# ESP32_S3-Mini-1.net
KiCad netlist of a schematic drawn in Altium Designer
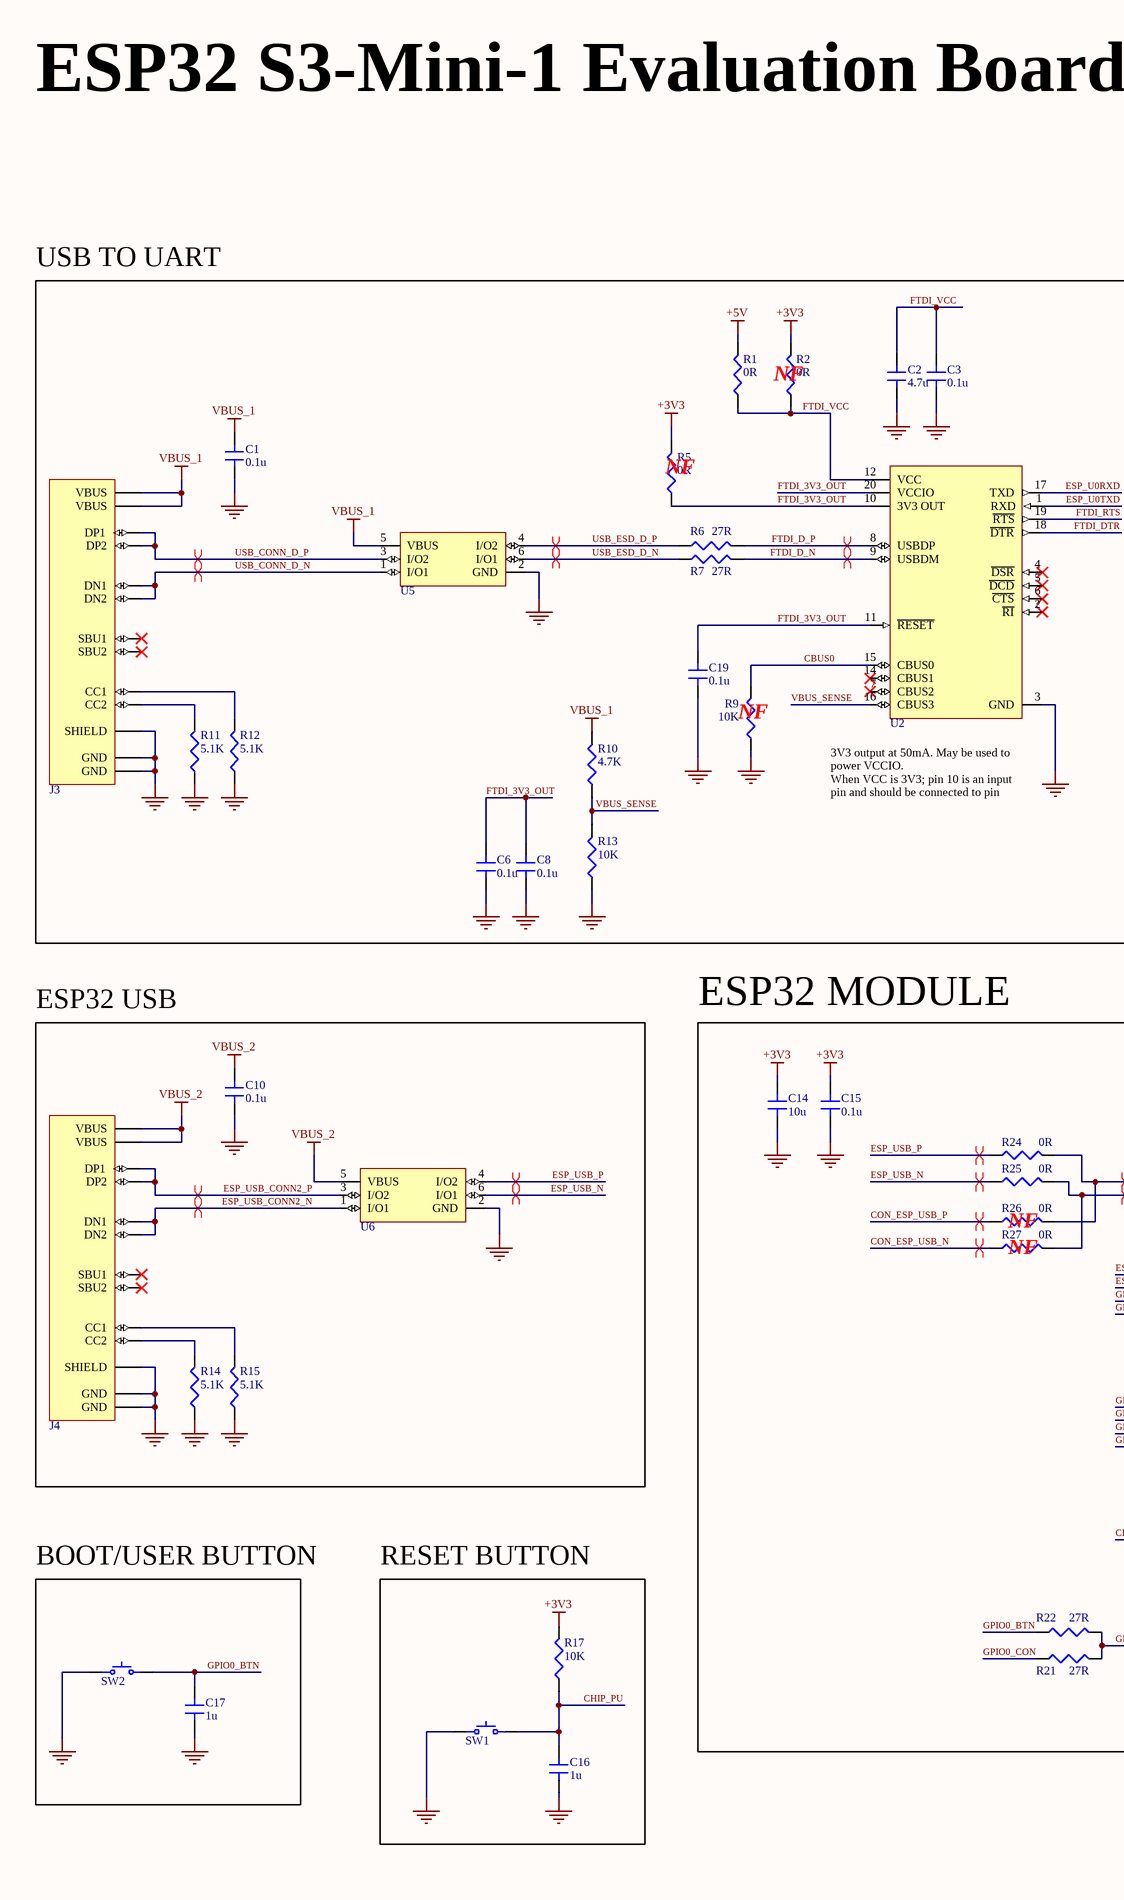
[diagram p0: ESP32 S3-Mini-1.SchDoc, left]
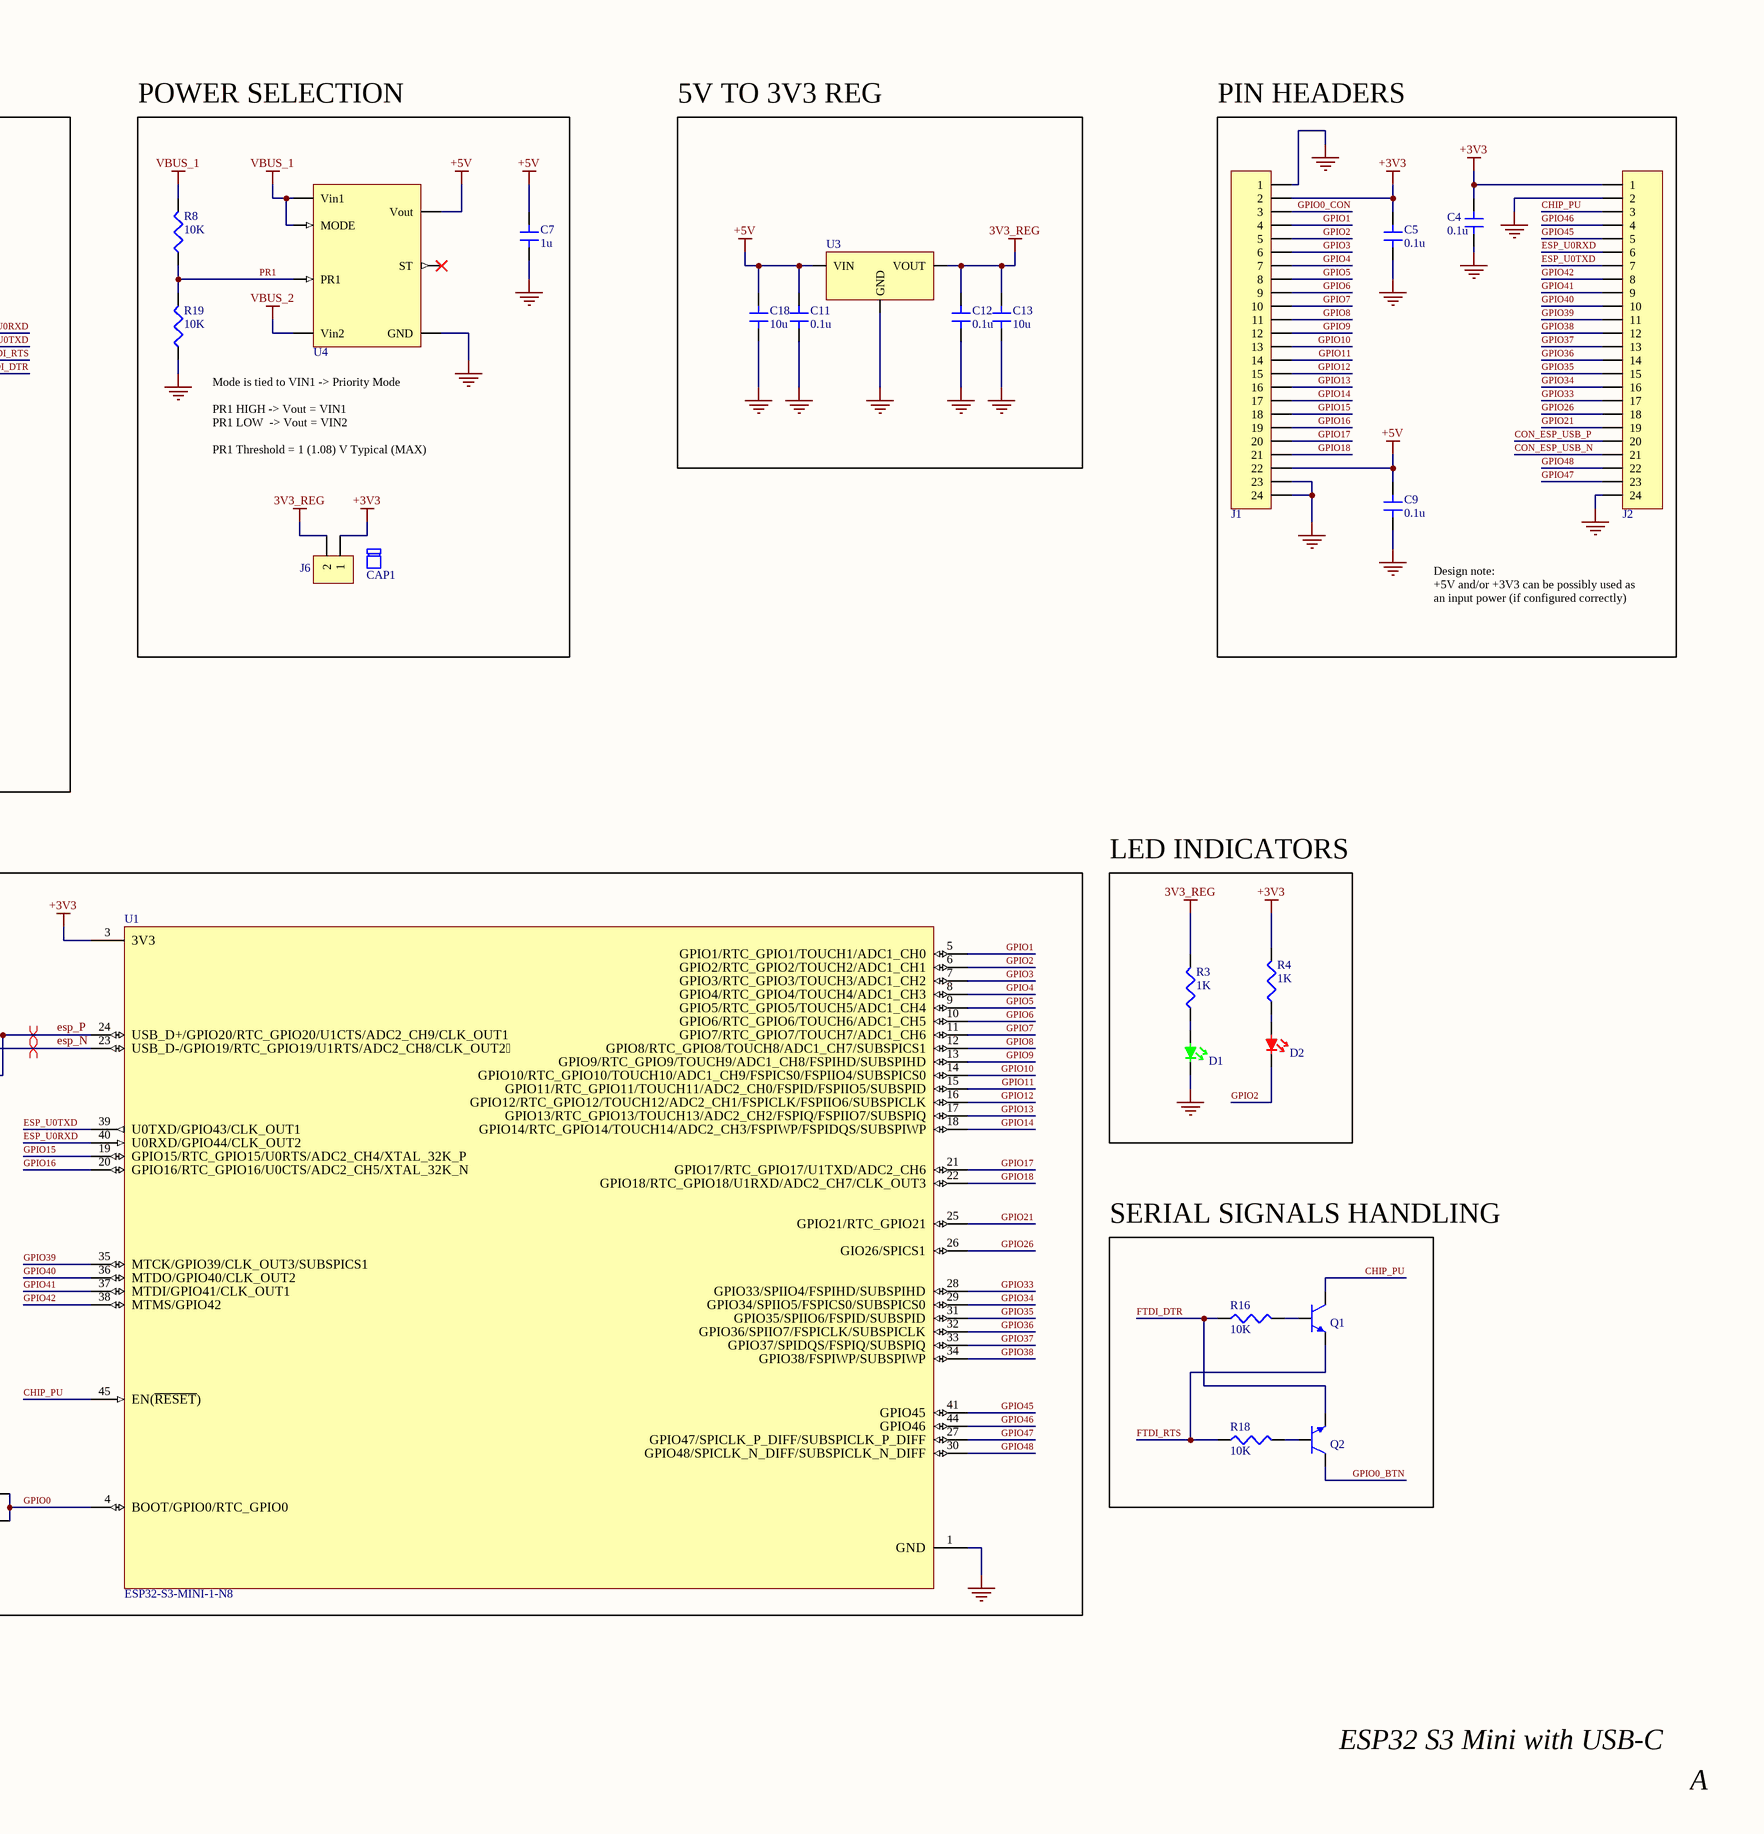
[diagram p1: ESP32 S3-Mini-1.SchDoc, right]

(export (version "E")
  (design (tool "Eeschema 10.0.6"))
  (components
    (comp (ref "C1")
      (value "0.1u")
      (footprint "0603-CAP")
      (description "50V 100nF X7R ±5% 0603 Multilayer Ceramic Capacitors MLCC - SMD/SMT ROHS")
      (fields (field (name "MANUFACTURER") "YAGEO") (field (name "MFR. PART #") "CC0603JRX7R9BB104"))
      (libsource (lib "Symbols") (part "CAP 0.1uF"))
    )
    (comp (ref "C2")
      (value "4.7u")
      (footprint "0603-CAP")
      (description "16V 4.7uF X5R ±10% 0603 Multilayer Ceramic Capacitors MLCC - SMD/SMT ROHS")
      (fields
        (field (name "MANUFACTURER") "Samsung Electro-Mechanics")
        (field (name "MFR. PART #") "CL10A475KO8NNNC")
      )
      (libsource (lib "Symbols") (part "CAP 4.7uF"))
    )
    (comp (ref "C3")
      (value "0.1u")
      (footprint "0603-CAP")
      (description "50V 100nF X7R ±5% 0603 Multilayer Ceramic Capacitors MLCC - SMD/SMT ROHS")
      (fields (field (name "MANUFACTURER") "YAGEO") (field (name "MFR. PART #") "CC0603JRX7R9BB104"))
      (libsource (lib "Symbols") (part "CAP 0.1uF"))
    )
    (comp (ref "C4")
      (value "0.1u")
      (footprint "0603-CAP")
      (description "50V 100nF X7R ±5% 0603 Multilayer Ceramic Capacitors MLCC - SMD/SMT ROHS")
      (fields (field (name "MANUFACTURER") "YAGEO") (field (name "MFR. PART #") "CC0603JRX7R9BB104"))
      (libsource (lib "Symbols") (part "CAP 0.1uF"))
    )
    (comp (ref "C5")
      (value "0.1u")
      (footprint "0603-CAP")
      (description "50V 100nF X7R ±5% 0603 Multilayer Ceramic Capacitors MLCC - SMD/SMT ROHS")
      (fields (field (name "MANUFACTURER") "YAGEO") (field (name "MFR. PART #") "CC0603JRX7R9BB104"))
      (libsource (lib "Symbols") (part "CAP 0.1uF"))
    )
    (comp (ref "C6")
      (value "0.1u")
      (footprint "0603-CAP")
      (description "50V 100nF X7R ±5% 0603 Multilayer Ceramic Capacitors MLCC - SMD/SMT ROHS")
      (fields (field (name "MANUFACTURER") "YAGEO") (field (name "MFR. PART #") "CC0603JRX7R9BB104"))
      (libsource (lib "Symbols") (part "CAP 0.1uF"))
    )
    (comp (ref "C7")
      (value "1u")
      (footprint "0603-CAP")
      (description "16V 1uF X7R ±5% 0603 Multilayer Ceramic Capacitors MLCC - SMD/SMT ROHS")
      (fields (field (name "MANUFACTURER") "YAGEO") (field (name "MFR. PART #") "CC0603JRX7R7BB105"))
      (libsource (lib "Symbols") (part "CAP 1uF"))
    )
    (comp (ref "C8")
      (value "0.1u")
      (footprint "0603-CAP")
      (description "50V 100nF X7R ±5% 0603 Multilayer Ceramic Capacitors MLCC - SMD/SMT ROHS")
      (fields (field (name "MANUFACTURER") "YAGEO") (field (name "MFR. PART #") "CC0603JRX7R9BB104"))
      (libsource (lib "Symbols") (part "CAP 0.1uF"))
    )
    (comp (ref "C9")
      (value "0.1u")
      (footprint "0603-CAP")
      (description "50V 100nF X7R ±5% 0603 Multilayer Ceramic Capacitors MLCC - SMD/SMT ROHS")
      (fields (field (name "MANUFACTURER") "YAGEO") (field (name "MFR. PART #") "CC0603JRX7R9BB104"))
      (libsource (lib "Symbols") (part "CAP 0.1uF"))
    )
    (comp (ref "C10")
      (value "0.1u")
      (footprint "0603-CAP")
      (description "50V 100nF X7R ±5% 0603 Multilayer Ceramic Capacitors MLCC - SMD/SMT ROHS")
      (fields (field (name "MANUFACTURER") "YAGEO") (field (name "MFR. PART #") "CC0603JRX7R9BB104"))
      (libsource (lib "Symbols") (part "CAP 0.1uF"))
    )
    (comp (ref "C11")
      (value "0.1u")
      (footprint "0603-CAP")
      (description "50V 100nF X7R ±5% 0603 Multilayer Ceramic Capacitors MLCC - SMD/SMT ROHS")
      (fields (field (name "MANUFACTURER") "YAGEO") (field (name "MFR. PART #") "CC0603JRX7R9BB104"))
      (libsource (lib "Symbols") (part "CAP 0.1uF"))
    )
    (comp (ref "C12")
      (value "0.1u")
      (footprint "0603-CAP")
      (description "50V 100nF X7R ±5% 0603 Multilayer Ceramic Capacitors MLCC - SMD/SMT ROHS")
      (fields (field (name "MANUFACTURER") "YAGEO") (field (name "MFR. PART #") "CC0603JRX7R9BB104"))
      (libsource (lib "Symbols") (part "CAP 0.1uF"))
    )
    (comp (ref "C13")
      (value "10u")
      (footprint "0603-CAP")
      (description "16V 10uF X5R ±10% 0603 Multilayer Ceramic Capacitors MLCC - SMD/SMT ROHS")
      (fields
        (field (name "MANUFACTURER") "Samsung Electro-Mechanics")
        (field (name "MFR. PART #") "CL10A106KO8NQNC")
      )
      (libsource (lib "Symbols") (part "CAP 10uF"))
    )
    (comp (ref "C14")
      (value "10u")
      (footprint "0603-CAP")
      (description "16V 10uF X5R ±10% 0603 Multilayer Ceramic Capacitors MLCC - SMD/SMT ROHS")
      (fields
        (field (name "MANUFACTURER") "Samsung Electro-Mechanics")
        (field (name "MFR. PART #") "CL10A106KO8NQNC")
      )
      (libsource (lib "Symbols") (part "CAP 10uF"))
    )
    (comp (ref "C15")
      (value "0.1u")
      (footprint "0603-CAP")
      (description "50V 100nF X7R ±5% 0603 Multilayer Ceramic Capacitors MLCC - SMD/SMT ROHS")
      (fields (field (name "MANUFACTURER") "YAGEO") (field (name "MFR. PART #") "CC0603JRX7R9BB104"))
      (libsource (lib "Symbols") (part "CAP 0.1uF"))
    )
    (comp (ref "C16")
      (value "1u")
      (footprint "0603-CAP")
      (description "16V 1uF X7R ±5% 0603 Multilayer Ceramic Capacitors MLCC - SMD/SMT ROHS")
      (fields (field (name "MANUFACTURER") "YAGEO") (field (name "MFR. PART #") "CC0603JRX7R7BB105"))
      (libsource (lib "Symbols") (part "CAP 1uF"))
    )
    (comp (ref "C17")
      (value "1u")
      (footprint "0603-CAP")
      (description "16V 1uF X7R ±5% 0603 Multilayer Ceramic Capacitors MLCC - SMD/SMT ROHS")
      (fields (field (name "MANUFACTURER") "YAGEO") (field (name "MFR. PART #") "CC0603JRX7R7BB105"))
      (libsource (lib "Symbols") (part "CAP 1uF"))
    )
    (comp (ref "C18")
      (value "10u")
      (footprint "0603-CAP")
      (description "16V 10uF X5R ±10% 0603 Multilayer Ceramic Capacitors MLCC - SMD/SMT ROHS")
      (fields
        (field (name "MANUFACTURER") "Samsung Electro-Mechanics")
        (field (name "MFR. PART #") "CL10A106KO8NQNC")
      )
      (libsource (lib "Symbols") (part "CAP 10uF"))
    )
    (comp (ref "C19")
      (value "0.1u")
      (footprint "0603-CAP")
      (description "50V 100nF X7R ±5% 0603 Multilayer Ceramic Capacitors MLCC - SMD/SMT ROHS")
      (fields (field (name "MANUFACTURER") "YAGEO") (field (name "MFR. PART #") "CC0603JRX7R9BB104"))
      (libsource (lib "Symbols") (part "CAP 0.1uF"))
    )
    (comp (ref "CAP1")
      (value "Cap Jumper")
      (description "Open top 3A 2.54mm P=2.54mm Shunts, Jumpers ROHS")
      (fields
        (field (name "MANUFACTURER") "BOOMELE(Boom Precision Elec)")
        (field (name "MFR. PART #") "2.54")
      )
      (libsource (lib "Symbols") (part "Cap Jumper"))
    )
    (comp (ref "D1")
      (value "GREEN")
      (footprint "1206-LED green")
      (fields (field (name "MANUFACTURER") "XINGLIGHT") (field (name "MFR. PART #") "XL-3216UGC"))
      (libsource (lib "Symbols") (part "LED GREEN"))
    )
    (comp (ref "D2")
      (value "RED")
      (footprint "1206-LED red")
      (fields (field (name "MANUFACTURER") "XINGLIGHT") (field (name "MFR. PART #") "XL-3216SURC"))
      (libsource (lib "Symbols") (part "LED RED"))
    )
    (comp (ref "J1")
      (value "1x24P male Pinheaders")
      (footprint "1x24P male pinheader")
      (fields
        (field (name "MANUFACTURER") "XKB Connection")
        (field (name "MFR. PART #") "X6511WV-24H-C60D30")
      )
      (libsource (lib "") (part "1x24P male Pinheaders_1"))
    )
    (comp (ref "J2")
      (value "1x24P male Pinheaders")
      (footprint "1x24P male pinheader")
      (fields
        (field (name "MANUFACTURER") "XKB Connection")
        (field (name "MFR. PART #") "X6511WV-24H-C60D30")
      )
      (libsource (lib "Symbols") (part "1x24P male Pinheaders"))
    )
    (comp (ref "J3")
      (value "USB Type C connector")
      (footprint "USB-C")
      (description "5A 1 16P Female Type-C SMD USB Connectors ROHS")
      (fields
        (field (name "MANUFACTURER") "Korean Hroparts Elec")
        (field (name "MFR. PART #") "TYPE-C-31-M-12")
      )
      (libsource (lib "Symbols") (part "USB Type C connector"))
    )
    (comp (ref "J4")
      (value "USB Type C connector")
      (footprint "USB-C")
      (description "5A 1 16P Female Type-C SMD USB Connectors ROHS")
      (fields
        (field (name "MANUFACTURER") "Korean Hroparts Elec")
        (field (name "MFR. PART #") "TYPE-C-31-M-12")
      )
      (libsource (lib "Symbols") (part "USB Type C connector"))
    )
    (comp (ref "J6")
      (value "1x2P male Pinheaders")
      (footprint "1x2P male pinheader")
      (description "3A Direct Insert Policy 2.54mm 2P 6mm 3mm 2.54mm Single Row 1x2P Plugin,P=2.54mm Pin Headers ROHS")
      (fields (field (name "MANUFACTURER") "DEALON") (field (name "MFR. PART #") "DZ254R-11-02-63"))
      (libsource (lib "Symbols") (part "1x2P male Pinheaders"))
    )
    (comp (ref "Q1")
      (value "BJT Transistor")
      (footprint "SOT-23")
      (description "25V 300mW 120@100mA,1V 1.5A NPN SOT-23 Bipolar (BJT) ROHS")
      (fields
        (field (name "MANUFACTURER") "Jiangsu Changjing Electronics Technology Co., Ltd.")
        (field (name "MFR. PART #") "SS8050-G(RANGE:120-200)")
      )
      (libsource (lib "Symbols") (part "BJT Transistor"))
    )
    (comp (ref "Q2")
      (value "BJT Transistor")
      (footprint "SOT-23")
      (description "25V 300mW 120@100mA,1V 1.5A NPN SOT-23 Bipolar (BJT) ROHS")
      (fields
        (field (name "MANUFACTURER") "Jiangsu Changjing Electronics Technology Co., Ltd.")
        (field (name "MFR. PART #") "SS8050-G(RANGE:120-200)")
      )
      (libsource (lib "Symbols") (part "BJT Transistor"))
    )
    (comp (ref "R1")
      (value "0R")
      (footprint "0402-RES")
      (description "62.5mW Thick Film Resistors 50V ±800ppm/℃ ±1% 0Ω 0402 Chip Resistor - Surface Mount ROHS")
      (fields
        (field (name "MANUFACTURER") "UNI-ROYAL(Uniroyal Elec)")
        (field (name "MFR. PART #") "0402WGF0000TCE")
      )
      (libsource (lib "Symbols") (part "Resistor 0R"))
    )
    (comp (ref "R2")
      (value "0R")
      (footprint "0402-RES")
      (description "62.5mW Thick Film Resistors 50V ±800ppm/℃ ±1% 0Ω 0402 Chip Resistor - Surface Mount ROHS")
      (fields
        (field (name "MANUFACTURER") "UNI-ROYAL(Uniroyal Elec)")
        (field (name "MFR. PART #") "0402WGF0000TCE")
      )
      (libsource (lib "Symbols") (part "Resistor 0R"))
    )
    (comp (ref "R3")
      (value "1K")
      (footprint "0603-RES")
      (description "100mW Thick Film Resistors 75V ±100ppm/℃ ±1% 1kΩ 0603 Chip Resistor - Surface Mount ROHS")
      (fields
        (field (name "MANUFACTURER") "UNI-ROYAL(Uniroyal Elec)")
        (field (name "MFR. PART #") "0603WAF1001T5E")
      )
      (libsource (lib "Symbols") (part "Resistor 1K"))
    )
    (comp (ref "R4")
      (value "1K")
      (footprint "0603-RES")
      (description "100mW Thick Film Resistors 75V ±100ppm/℃ ±1% 1kΩ 0603 Chip Resistor - Surface Mount ROHS")
      (fields
        (field (name "MANUFACTURER") "UNI-ROYAL(Uniroyal Elec)")
        (field (name "MFR. PART #") "0603WAF1001T5E")
      )
      (libsource (lib "Symbols") (part "Resistor 1K"))
    )
    (comp (ref "R5")
      (value "0R")
      (footprint "0402-RES")
      (description "62.5mW Thick Film Resistors 50V ±800ppm/℃ ±1% 0Ω 0402 Chip Resistor - Surface Mount ROHS")
      (fields
        (field (name "MANUFACTURER") "UNI-ROYAL(Uniroyal Elec)")
        (field (name "MFR. PART #") "0402WGF0000TCE")
      )
      (libsource (lib "Symbols") (part "Resistor 0R"))
    )
    (comp (ref "R6")
      (value "27R")
      (footprint "0603-RES")
      (description "100mW Thick Film Resistors 75V ±1% ±200ppm/℃ 27Ω 0603 Chip Resistor - Surface Mount ROHS")
      (fields
        (field (name "MANUFACTURER") "UNI-ROYAL(Uniroyal Elec)")
        (field (name "MFR. PART #") "0603WAF270JT5E")
      )
      (libsource (lib "Symbols") (part "Resistor 27R"))
    )
    (comp (ref "R7")
      (value "27R")
      (footprint "0603-RES")
      (description "100mW Thick Film Resistors 75V ±1% ±200ppm/℃ 27Ω 0603 Chip Resistor - Surface Mount ROHS")
      (fields
        (field (name "MANUFACTURER") "UNI-ROYAL(Uniroyal Elec)")
        (field (name "MFR. PART #") "0603WAF270JT5E")
      )
      (libsource (lib "Symbols") (part "Resistor 27R"))
    )
    (comp (ref "R8")
      (value "10K")
      (footprint "0603-RES")
      (description "100mW Thick Film Resistors 75V ±100ppm/℃ ±1% 10kΩ 0603 Chip Resistor - Surface Mount ROHS")
      (fields
        (field (name "MANUFACTURER") "UNI-ROYAL(Uniroyal Elec)")
        (field (name "MFR. PART #") "0603WAF1002T5E")
      )
      (libsource (lib "Symbols") (part "Resistor 10K"))
    )
    (comp (ref "R9")
      (value "10K")
      (footprint "0603-RES")
      (description "100mW Thick Film Resistors 75V ±100ppm/℃ ±1% 10kΩ 0603 Chip Resistor - Surface Mount ROHS")
      (fields
        (field (name "MANUFACTURER") "UNI-ROYAL(Uniroyal Elec)")
        (field (name "MFR. PART #") "0603WAF1002T5E")
      )
      (libsource (lib "Symbols") (part "Resistor 10K"))
    )
    (comp (ref "R10")
      (value "4.7K")
      (footprint "0603-RES")
      (description "100mW Thick Film Resistors 75V ±100ppm/℃ ±1% 4.7kΩ 0603 Chip Resistor - Surface Mount ROHS")
      (fields
        (field (name "MANUFACTURER") "UNI-ROYAL(Uniroyal Elec)")
        (field (name "MFR. PART #") "0603WAF4701T5E")
      )
      (libsource (lib "Symbols") (part "Resistor 4.7K"))
    )
    (comp (ref "R11")
      (value "5.1K")
      (footprint "0603-RES")
      (description "100mW Thick Film Resistors 75V ±100ppm/℃ ±5% 5.1kΩ 0603 Chip Resistor - Surface Mount ROHS")
      (fields
        (field (name "MANUFACTURER") "UNI-ROYAL(Uniroyal Elec)")
        (field (name "MFR. PART #") "0603WAJ0512T5E")
      )
      (libsource (lib "Symbols") (part "Resistor 5.1K"))
    )
    (comp (ref "R12")
      (value "5.1K")
      (footprint "0603-RES")
      (description "100mW Thick Film Resistors 75V ±100ppm/℃ ±5% 5.1kΩ 0603 Chip Resistor - Surface Mount ROHS")
      (fields
        (field (name "MANUFACTURER") "UNI-ROYAL(Uniroyal Elec)")
        (field (name "MFR. PART #") "0603WAJ0512T5E")
      )
      (libsource (lib "Symbols") (part "Resistor 5.1K"))
    )
    (comp (ref "R13")
      (value "10K")
      (footprint "0603-RES")
      (description "100mW Thick Film Resistors 75V ±100ppm/℃ ±1% 10kΩ 0603 Chip Resistor - Surface Mount ROHS")
      (fields
        (field (name "MANUFACTURER") "UNI-ROYAL(Uniroyal Elec)")
        (field (name "MFR. PART #") "0603WAF1002T5E")
      )
      (libsource (lib "Symbols") (part "Resistor 10K"))
    )
    (comp (ref "R14")
      (value "5.1K")
      (footprint "0603-RES")
      (description "100mW Thick Film Resistors 75V ±100ppm/℃ ±5% 5.1kΩ 0603 Chip Resistor - Surface Mount ROHS")
      (fields
        (field (name "MANUFACTURER") "UNI-ROYAL(Uniroyal Elec)")
        (field (name "MFR. PART #") "0603WAJ0512T5E")
      )
      (libsource (lib "Symbols") (part "Resistor 5.1K"))
    )
    (comp (ref "R15")
      (value "5.1K")
      (footprint "0603-RES")
      (description "100mW Thick Film Resistors 75V ±100ppm/℃ ±5% 5.1kΩ 0603 Chip Resistor - Surface Mount ROHS")
      (fields
        (field (name "MANUFACTURER") "UNI-ROYAL(Uniroyal Elec)")
        (field (name "MFR. PART #") "0603WAJ0512T5E")
      )
      (libsource (lib "Symbols") (part "Resistor 5.1K"))
    )
    (comp (ref "R16")
      (value "10K")
      (footprint "0603-RES")
      (description "100mW Thick Film Resistors 75V ±100ppm/℃ ±1% 10kΩ 0603 Chip Resistor - Surface Mount ROHS")
      (fields
        (field (name "MANUFACTURER") "UNI-ROYAL(Uniroyal Elec)")
        (field (name "MFR. PART #") "0603WAF1002T5E")
      )
      (libsource (lib "Symbols") (part "Resistor 10K"))
    )
    (comp (ref "R17")
      (value "10K")
      (footprint "0603-RES")
      (description "100mW Thick Film Resistors 75V ±100ppm/℃ ±1% 10kΩ 0603 Chip Resistor - Surface Mount ROHS")
      (fields
        (field (name "MANUFACTURER") "UNI-ROYAL(Uniroyal Elec)")
        (field (name "MFR. PART #") "0603WAF1002T5E")
      )
      (libsource (lib "Symbols") (part "Resistor 10K"))
    )
    (comp (ref "R18")
      (value "10K")
      (footprint "0603-RES")
      (description "100mW Thick Film Resistors 75V ±100ppm/℃ ±1% 10kΩ 0603 Chip Resistor - Surface Mount ROHS")
      (fields
        (field (name "MANUFACTURER") "UNI-ROYAL(Uniroyal Elec)")
        (field (name "MFR. PART #") "0603WAF1002T5E")
      )
      (libsource (lib "Symbols") (part "Resistor 10K"))
    )
    (comp (ref "R19")
      (value "10K")
      (footprint "0603-RES")
      (description "100mW Thick Film Resistors 75V ±100ppm/℃ ±1% 10kΩ 0603 Chip Resistor - Surface Mount ROHS")
      (fields
        (field (name "MANUFACTURER") "UNI-ROYAL(Uniroyal Elec)")
        (field (name "MFR. PART #") "0603WAF1002T5E")
      )
      (libsource (lib "Symbols") (part "Resistor 10K"))
    )
    (comp (ref "R21")
      (value "27R")
      (footprint "0603-RES")
      (description "100mW Thick Film Resistors 75V ±1% ±200ppm/℃ 27Ω 0603 Chip Resistor - Surface Mount ROHS")
      (fields
        (field (name "MANUFACTURER") "UNI-ROYAL(Uniroyal Elec)")
        (field (name "MFR. PART #") "0603WAF270JT5E")
      )
      (libsource (lib "Symbols") (part "Resistor 27R"))
    )
    (comp (ref "R22")
      (value "27R")
      (footprint "0603-RES")
      (description "100mW Thick Film Resistors 75V ±1% ±200ppm/℃ 27Ω 0603 Chip Resistor - Surface Mount ROHS")
      (fields
        (field (name "MANUFACTURER") "UNI-ROYAL(Uniroyal Elec)")
        (field (name "MFR. PART #") "0603WAF270JT5E")
      )
      (libsource (lib "Symbols") (part "Resistor 27R"))
    )
    (comp (ref "R24")
      (value "0R")
      (footprint "0402-RES")
      (description "62.5mW Thick Film Resistors 50V ±800ppm/℃ ±1% 0Ω 0402 Chip Resistor - Surface Mount ROHS")
      (fields
        (field (name "MANUFACTURER") "UNI-ROYAL(Uniroyal Elec)")
        (field (name "MFR. PART #") "0402WGF0000TCE")
      )
      (libsource (lib "Symbols") (part "Resistor 0R"))
    )
    (comp (ref "R25")
      (value "0R")
      (footprint "0402-RES")
      (description "62.5mW Thick Film Resistors 50V ±800ppm/℃ ±1% 0Ω 0402 Chip Resistor - Surface Mount ROHS")
      (fields
        (field (name "MANUFACTURER") "UNI-ROYAL(Uniroyal Elec)")
        (field (name "MFR. PART #") "0402WGF0000TCE")
      )
      (libsource (lib "Symbols") (part "Resistor 0R"))
    )
    (comp (ref "R26")
      (value "0R")
      (footprint "0402-RES")
      (description "62.5mW Thick Film Resistors 50V ±800ppm/℃ ±1% 0Ω 0402 Chip Resistor - Surface Mount ROHS")
      (fields
        (field (name "MANUFACTURER") "UNI-ROYAL(Uniroyal Elec)")
        (field (name "MFR. PART #") "0402WGF0000TCE")
      )
      (libsource (lib "Symbols") (part "Resistor 0R"))
    )
    (comp (ref "R27")
      (value "0R")
      (footprint "0402-RES")
      (description "62.5mW Thick Film Resistors 50V ±800ppm/℃ ±1% 0Ω 0402 Chip Resistor - Surface Mount ROHS")
      (fields
        (field (name "MANUFACTURER") "UNI-ROYAL(Uniroyal Elec)")
        (field (name "MFR. PART #") "0402WGF0000TCE")
      )
      (libsource (lib "Symbols") (part "Resistor 0R"))
    )
    (comp (ref "SW1")
      (value "Tactile Switch")
      (footprint "Tactile Switch")
      (fields (field (name "MANUFACTURER") "XKB Connection") (field (name "MFR. PART #") "TS-1187A-B-A-B"))
      (libsource (lib "Symbols") (part "Tactile Switch"))
    )
    (comp (ref "SW2")
      (value "Tactile Switch")
      (footprint "Tactile Switch")
      (fields (field (name "MANUFACTURER") "XKB Connection") (field (name "MFR. PART #") "TS-1187A-B-A-B"))
      (libsource (lib "Symbols") (part "Tactile Switch"))
    )
    (comp (ref "U1")
      (value "ESP32-S3-MINI-1-N8")
      (footprint "ESP32-S3-MINI-1-N8")
      (description "20.5dBm ESP32-S3FN8 chip 2.4GHz SMD-41P WiFi Modules ROHS")
      (fields (field (name "MANUFACTURER") "Espressif Systems"))
      (libsource (lib "Symbols") (part "ESP32-S3-MINI"))
    )
    (comp (ref "U2")
      (value "FTDI USB to UART")
      (footprint "QFN-20-EP(4x4)")
      (description "USB to UART UART QFN-20-EP(4x4) USB Converters ROHS")
      (fields (field (name "MANUFACTURER") "FTDI") (field (name "MFR. PART #") "FT231XQ-R"))
      (libsource (lib "Symbols") (part "FTDI USB to UART"))
    )
    (comp (ref "U3")
      (value "3V3 LDO")
      (footprint "TO-252-2(DPAK)")
      (fields (field (name "MANUFACTURER") "STMicroelectronics") (field (name "MFR. PART #") "LD1086DT33TR"))
      (libsource (lib "Symbols") (part "3V3 LDO"))
    )
    (comp (ref "U4")
      (value "Power Switchover")
      (footprint "SOT-583")
      (description "1.6V~5.5V 42mΩ 2.5A 1 SOT-583 Power Distribution Switches ROHS")
      (fields (field (name "MANUFACTURER") "Texas Instruments") (field (name "MFR. PART #") "TPS2116DRLR"))
      (libsource (lib "Symbols") (part "Power Switchover"))
    )
    (comp (ref "U5")
      (value "3 Channels ESD Protection")
      (footprint "SOT-23-6")
      (description "5A 17V 6V Unidirectional 5.25V SOT-23-6 Electrostatic and Surge Protection (TVS/ESD) ROHS")
      (fields (field (name "MANUFACTURER") "STMicroelectronics") (field (name "MFR. PART #") "USBLC6-2SC6"))
      (libsource (lib "Symbols") (part "3 Channels ESD Protection"))
    )
    (comp (ref "U6")
      (value "3 Channels ESD Protection")
      (footprint "SOT-23-6")
      (description "5A 17V 6V Unidirectional 5.25V SOT-23-6 Electrostatic and Surge Protection (TVS/ESD) ROHS")
      (fields (field (name "MANUFACTURER") "STMicroelectronics") (field (name "MFR. PART #") "USBLC6-2SC6"))
      (libsource (lib "Symbols") (part "3 Channels ESD Protection"))
    )
  )
  (nets
    (net (code "1") (name "+3V3") (class "Default")
      (node (ref "C14") (pin "2") (pinfunction "2_2") (pintype "passive"))
      (node (ref "C15") (pin "2") (pinfunction "2_2") (pintype "passive"))
      (node (ref "C4") (pin "2") (pinfunction "2_2") (pintype "passive"))
      (node (ref "C5") (pin "2") (pinfunction "2_2") (pintype "passive"))
      (node (ref "J1") (pin "2") (pinfunction "2_2") (pintype "passive"))
      (node (ref "J2") (pin "1") (pinfunction "1_1") (pintype "passive"))
      (node (ref "J6") (pin "1") (pinfunction "1_1") (pintype "passive"))
      (node (ref "R17") (pin "2") (pinfunction "2_2") (pintype "passive"))
      (node (ref "R2") (pin "2") (pinfunction "2_2") (pintype "passive"))
      (node (ref "R4") (pin "2") (pinfunction "2_2") (pintype "passive"))
      (node (ref "R5") (pin "2") (pinfunction "2_2") (pintype "passive"))
      (node (ref "U1") (pin "3") (pinfunction "3V3_3") (pintype "power_in"))
    )
    (net (code "2") (name "+5V") (class "Default")
      (node (ref "C11") (pin "2") (pinfunction "2_2") (pintype "passive"))
      (node (ref "C18") (pin "2") (pinfunction "2_2") (pintype "passive"))
      (node (ref "C7") (pin "2") (pinfunction "2_2") (pintype "passive"))
      (node (ref "C9") (pin "2") (pinfunction "2_2") (pintype "passive"))
      (node (ref "J1") (pin "22") (pinfunction "22_22") (pintype "passive"))
      (node (ref "R1") (pin "2") (pinfunction "2_2") (pintype "passive"))
      (node (ref "U3") (pin "2") (pinfunction "VIN_2") (pintype "power_in"))
      (node (ref "U4") (pin "2") (pinfunction "Vout_2") (pintype "power_in"))
    )
    (net (code "3") (name "/CBUS0") (class "Default")
      (node (ref "R9") (pin "2") (pinfunction "2_2") (pintype "passive"))
      (node (ref "U2") (pin "15") (pinfunction "CBUS0_15") (pintype "bidirectional"))
    )
    (net (code "4") (name "/CHIP_PU") (class "Default")
      (node (ref "C16") (pin "2") (pinfunction "2_2") (pintype "passive"))
      (node (ref "J2") (pin "3") (pinfunction "3_3") (pintype "passive"))
      (node (ref "Q1") (pin "3") (pinfunction "3_3") (pintype "passive"))
      (node (ref "R17") (pin "1") (pinfunction "1_1") (pintype "passive"))
      (node (ref "SW1") (pin "2") (pinfunction "2_2") (pintype "passive"))
      (node (ref "U1") (pin "45") (pinfunction "EN(~{RESET})_45") (pintype "input"))
    )
    (net (code "5") (name "/CON_ESP_USB_N") (class "Default")
      (node (ref "J2") (pin "21") (pinfunction "21_21") (pintype "passive"))
      (node (ref "R27") (pin "1") (pinfunction "1_1") (pintype "passive"))
    )
    (net (code "6") (name "/CON_ESP_USB_P") (class "Default")
      (node (ref "J2") (pin "20") (pinfunction "20_20") (pintype "passive"))
      (node (ref "R26") (pin "1") (pinfunction "1_1") (pintype "passive"))
    )
    (net (code "7") (name "/ESP_U0RXD") (class "Default")
      (node (ref "J2") (pin "6") (pinfunction "6_6") (pintype "passive"))
      (node (ref "U1") (pin "40") (pinfunction "U0RXD/GPIO44/CLK_OUT2_40") (pintype "input"))
      (node (ref "U2") (pin "17") (pinfunction "TXD_17") (pintype "output"))
    )
    (net (code "8") (name "/ESP_U0TXD") (class "Default")
      (node (ref "J2") (pin "7") (pinfunction "7_7") (pintype "passive"))
      (node (ref "U1") (pin "39") (pinfunction "U0TXD/GPIO43/CLK_OUT1_39") (pintype "output"))
      (node (ref "U2") (pin "1") (pinfunction "RXD_1") (pintype "input"))
    )
    (net (code "9") (name "/ESP_USB_CONN2_N") (class "Default")
      (node (ref "J4") (pin "A7") (pinfunction "DN1_A7") (pintype "bidirectional"))
      (node (ref "J4") (pin "B7") (pinfunction "DN2_B7") (pintype "bidirectional"))
      (node (ref "U6") (pin "1") (pinfunction "I/O1_1") (pintype "bidirectional"))
    )
    (net (code "10") (name "/ESP_USB_CONN2_P") (class "Default")
      (node (ref "J4") (pin "A6") (pinfunction "DP1_A6") (pintype "bidirectional"))
      (node (ref "J4") (pin "B6") (pinfunction "DP2_B6") (pintype "bidirectional"))
      (node (ref "U6") (pin "3") (pinfunction "I/O2_3") (pintype "bidirectional"))
    )
    (net (code "11") (name "/ESP_USB_N") (class "Default")
      (node (ref "R25") (pin "1") (pinfunction "1_1") (pintype "passive"))
      (node (ref "U6") (pin "6") (pinfunction "I/O1_6") (pintype "bidirectional"))
    )
    (net (code "12") (name "/ESP_USB_P") (class "Default")
      (node (ref "R24") (pin "1") (pinfunction "1_1") (pintype "passive"))
      (node (ref "U6") (pin "4") (pinfunction "I/O2_4") (pintype "bidirectional"))
    )
    (net (code "13") (name "/FTDI_3V3_OUT") (class "Default")
      (node (ref "C19") (pin "2") (pinfunction "2_2") (pintype "passive"))
      (node (ref "C6") (pin "2") (pinfunction "2_2") (pintype "passive"))
      (node (ref "C8") (pin "2") (pinfunction "2_2") (pintype "passive"))
      (node (ref "R5") (pin "1") (pinfunction "1_1") (pintype "passive"))
      (node (ref "U2") (pin "10") (pinfunction "3V3_OUT_10") (pintype "power_in"))
      (node (ref "U2") (pin "11") (pinfunction "~{RESET}_11") (pintype "input"))
      (node (ref "U2") (pin "20") (pinfunction "VCCIO_20") (pintype "power_in"))
    )
    (net (code "14") (name "/FTDI_DTR") (class "Default")
      (node (ref "Q2") (pin "2") (pinfunction "2_2") (pintype "passive"))
      (node (ref "R16") (pin "1") (pinfunction "1_1") (pintype "passive"))
      (node (ref "U2") (pin "18") (pinfunction "~{DTR}_18") (pintype "output"))
    )
    (net (code "15") (name "/FTDI_D_N") (class "Default")
      (node (ref "R7") (pin "2") (pinfunction "2_2") (pintype "passive"))
      (node (ref "U2") (pin "9") (pinfunction "USBDM_9") (pintype "bidirectional"))
    )
    (net (code "16") (name "/FTDI_D_P") (class "Default")
      (node (ref "R6") (pin "2") (pinfunction "2_2") (pintype "passive"))
      (node (ref "U2") (pin "8") (pinfunction "USBDP_8") (pintype "bidirectional"))
    )
    (net (code "17") (name "/FTDI_RTS") (class "Default")
      (node (ref "Q1") (pin "2") (pinfunction "2_2") (pintype "passive"))
      (node (ref "R18") (pin "1") (pinfunction "1_1") (pintype "passive"))
      (node (ref "U2") (pin "19") (pinfunction "~{RTS}_19") (pintype "output"))
    )
    (net (code "18") (name "/FTDI_VCC") (class "Default")
      (node (ref "C2") (pin "2") (pinfunction "2_2") (pintype "passive"))
      (node (ref "C3") (pin "2") (pinfunction "2_2") (pintype "passive"))
      (node (ref "R1") (pin "1") (pinfunction "1_1") (pintype "passive"))
      (node (ref "R2") (pin "1") (pinfunction "1_1") (pintype "passive"))
      (node (ref "U2") (pin "12") (pinfunction "VCC_12") (pintype "power_in"))
    )
    (net (code "19") (name "/GPIO0") (class "Default")
      (node (ref "R21") (pin "2") (pinfunction "2_2") (pintype "passive"))
      (node (ref "R22") (pin "2") (pinfunction "2_2") (pintype "passive"))
      (node (ref "U1") (pin "4") (pinfunction "BOOT/GPIO0/RTC_GPIO0_4") (pintype "bidirectional"))
    )
    (net (code "20") (name "/GPIO0_BTN") (class "Default")
      (node (ref "C17") (pin "2") (pinfunction "2_2") (pintype "passive"))
      (node (ref "Q2") (pin "3") (pinfunction "3_3") (pintype "passive"))
      (node (ref "R22") (pin "1") (pinfunction "1_1") (pintype "passive"))
      (node (ref "SW2") (pin "2") (pinfunction "2_2") (pintype "passive"))
    )
    (net (code "21") (name "/GPIO0_CON") (class "Default")
      (node (ref "J1") (pin "3") (pinfunction "3_3") (pintype "passive"))
      (node (ref "R21") (pin "1") (pinfunction "1_1") (pintype "passive"))
    )
    (net (code "22") (name "/GPIO1") (class "Default")
      (node (ref "J1") (pin "4") (pinfunction "4_4") (pintype "passive"))
      (node (ref "U1") (pin "5") (pinfunction "GPIO1/RTC_GPIO1/TOUCH1/ADC1_CH0_5") (pintype "bidirectional"))
    )
    (net (code "23") (name "/GPIO2") (class "Default")
      (node (ref "D2") (pin "2") (pinfunction "2_2") (pintype "passive"))
      (node (ref "J1") (pin "5") (pinfunction "5_5") (pintype "passive"))
      (node (ref "U1") (pin "6") (pinfunction "GPIO2/RTC_GPIO2/TOUCH2/ADC1_CH1_6") (pintype "bidirectional"))
    )
    (net (code "24") (name "/GPIO3") (class "Default")
      (node (ref "J1") (pin "6") (pinfunction "6_6") (pintype "passive"))
      (node (ref "U1") (pin "7") (pinfunction "GPIO3/RTC_GPIO3/TOUCH3/ADC1_CH2_7") (pintype "bidirectional"))
    )
    (net (code "25") (name "/GPIO4") (class "Default")
      (node (ref "J1") (pin "7") (pinfunction "7_7") (pintype "passive"))
      (node (ref "U1") (pin "8") (pinfunction "GPIO4/RTC_GPIO4/TOUCH4/ADC1_CH3_8") (pintype "bidirectional"))
    )
    (net (code "26") (name "/GPIO5") (class "Default")
      (node (ref "J1") (pin "8") (pinfunction "8_8") (pintype "passive"))
      (node (ref "U1") (pin "9") (pinfunction "GPIO5/RTC_GPIO5/TOUCH5/ADC1_CH4_9") (pintype "bidirectional"))
    )
    (net (code "27") (name "/GPIO6") (class "Default")
      (node (ref "J1") (pin "9") (pinfunction "9_9") (pintype "passive"))
      (node (ref "U1") (pin "10") (pinfunction "GPIO6/RTC_GPIO6/TOUCH6/ADC1_CH5_10") (pintype "bidirectional"))
    )
    (net (code "28") (name "/GPIO7") (class "Default")
      (node (ref "J1") (pin "10") (pinfunction "10_10") (pintype "passive"))
      (node (ref "U1") (pin "11") (pinfunction "GPIO7/RTC_GPIO7/TOUCH7/ADC1_CH6_11") (pintype "bidirectional"))
    )
    (net (code "29") (name "/GPIO8") (class "Default")
      (node (ref "J1") (pin "11") (pinfunction "11_11") (pintype "passive"))
      (node (ref "U1") (pin "12") (pinfunction "GPIO8/RTC_GPIO8/TOUCH8/ADC1_CH7/SUBSPICS1_12") (pintype "bidirectional"))
    )
    (net (code "30") (name "/GPIO9") (class "Default")
      (node (ref "J1") (pin "12") (pinfunction "12_12") (pintype "passive"))
      (node (ref "U1") (pin "13") (pinfunction "GPIO9/RTC_GPIO9/TOUCH9/ADC1_CH8/FSPIHD/SUBSPIHD_13") (pintype "bidirectional"))
    )
    (net (code "31") (name "/GPIO10") (class "Default")
      (node (ref "J1") (pin "13") (pinfunction "13_13") (pintype "passive"))
      (node (ref "U1") (pin "14") (pinfunction "GPIO10/RTC_GPIO10/TOUCH10/ADC1_CH9/FSPICS0/FSPIIO4/SUBSPICS0_14") (pintype "bidirectional"))
    )
    (net (code "32") (name "/GPIO11") (class "Default")
      (node (ref "J1") (pin "14") (pinfunction "14_14") (pintype "passive"))
      (node (ref "U1") (pin "15") (pinfunction "GPIO11/RTC_GPIO11/TOUCH11/ADC2_CH0/FSPID/FSPIIO5/SUBSPID_15") (pintype "bidirectional"))
    )
    (net (code "33") (name "/GPIO12") (class "Default")
      (node (ref "J1") (pin "15") (pinfunction "15_15") (pintype "passive"))
      (node (ref "U1") (pin "16") (pinfunction "GPIO12/RTC_GPIO12/TOUCH12/ADC2_CH1/FSPICLK/FSPIIO6/SUBSPICLK_16") (pintype "bidirectional"))
    )
    (net (code "34") (name "/GPIO13") (class "Default")
      (node (ref "J1") (pin "16") (pinfunction "16_16") (pintype "passive"))
      (node (ref "U1") (pin "17") (pinfunction "GPIO13/RTC_GPIO13/TOUCH13/ADC2_CH2/FSPIQ/FSPIIO7/SUBSPIQ_17") (pintype "bidirectional"))
    )
    (net (code "35") (name "/GPIO14") (class "Default")
      (node (ref "J1") (pin "17") (pinfunction "17_17") (pintype "passive"))
      (node (ref "U1") (pin "18") (pinfunction "GPIO14/RTC_GPIO14/TOUCH14/ADC2_CH3/FSPIWP/FSPIDQS/SUBSPIWP_18") (pintype "bidirectional"))
    )
    (net (code "36") (name "/GPIO15") (class "Default")
      (node (ref "J1") (pin "18") (pinfunction "18_18") (pintype "passive"))
      (node (ref "U1") (pin "19") (pinfunction "GPIO15/RTC_GPIO15/U0RTS/ADC2_CH4/XTAL_32K_P_19") (pintype "bidirectional"))
    )
    (net (code "37") (name "/GPIO16") (class "Default")
      (node (ref "J1") (pin "19") (pinfunction "19_19") (pintype "passive"))
      (node (ref "U1") (pin "20") (pinfunction "GPIO16/RTC_GPIO16/U0CTS/ADC2_CH5/XTAL_32K_N_20") (pintype "bidirectional"))
    )
    (net (code "38") (name "/GPIO17") (class "Default")
      (node (ref "J1") (pin "20") (pinfunction "20_20") (pintype "passive"))
      (node (ref "U1") (pin "21") (pinfunction "GPIO17/RTC_GPIO17/U1TXD/ADC2_CH6_21") (pintype "bidirectional"))
    )
    (net (code "39") (name "/GPIO18") (class "Default")
      (node (ref "J1") (pin "21") (pinfunction "21_21") (pintype "passive"))
      (node (ref "U1") (pin "22") (pinfunction "GPIO18/RTC_GPIO18/U1RXD/ADC2_CH7/CLK_OUT3_22") (pintype "bidirectional"))
    )
    (net (code "40") (name "/GPIO21") (class "Default")
      (node (ref "J2") (pin "19") (pinfunction "19_19") (pintype "passive"))
      (node (ref "U1") (pin "25") (pinfunction "GPIO21/RTC_GPIO21_25") (pintype "bidirectional"))
    )
    (net (code "41") (name "/GPIO26") (class "Default")
      (node (ref "J2") (pin "18") (pinfunction "18_18") (pintype "passive"))
      (node (ref "U1") (pin "26") (pinfunction "GIO26/SPICS1_26") (pintype "bidirectional"))
    )
    (net (code "42") (name "/GPIO33") (class "Default")
      (node (ref "J2") (pin "17") (pinfunction "17_17") (pintype "passive"))
      (node (ref "U1") (pin "28") (pinfunction "GPIO33/SPIIO4/FSPIHD/SUBSPIHD_28") (pintype "bidirectional"))
    )
    (net (code "43") (name "/GPIO34") (class "Default")
      (node (ref "J2") (pin "16") (pinfunction "16_16") (pintype "passive"))
      (node (ref "U1") (pin "29") (pinfunction "GPIO34/SPIIO5/FSPICS0/SUBSPICS0_29") (pintype "bidirectional"))
    )
    (net (code "44") (name "/GPIO35") (class "Default")
      (node (ref "J2") (pin "15") (pinfunction "15_15") (pintype "passive"))
      (node (ref "U1") (pin "31") (pinfunction "GPIO35/SPIIO6/FSPID/SUBSPID_31") (pintype "bidirectional"))
    )
    (net (code "45") (name "/GPIO36") (class "Default")
      (node (ref "J2") (pin "14") (pinfunction "14_14") (pintype "passive"))
      (node (ref "U1") (pin "32") (pinfunction "GPIO36/SPIIO7/FSPICLK/SUBSPICLK_32") (pintype "bidirectional"))
    )
    (net (code "46") (name "/GPIO37") (class "Default")
      (node (ref "J2") (pin "13") (pinfunction "13_13") (pintype "passive"))
      (node (ref "U1") (pin "33") (pinfunction "GPIO37/SPIDQS/FSPIQ/SUBSPIQ_33") (pintype "bidirectional"))
    )
    (net (code "47") (name "/GPIO38") (class "Default")
      (node (ref "J2") (pin "12") (pinfunction "12_12") (pintype "passive"))
      (node (ref "U1") (pin "34") (pinfunction "GPIO38/FSPIWP/SUBSPIWP_34") (pintype "bidirectional"))
    )
    (net (code "48") (name "/GPIO39") (class "Default")
      (node (ref "J2") (pin "11") (pinfunction "11_11") (pintype "passive"))
      (node (ref "U1") (pin "35") (pinfunction "MTCK/GPIO39/CLK_OUT3/SUBSPICS1_35") (pintype "bidirectional"))
    )
    (net (code "49") (name "/GPIO40") (class "Default")
      (node (ref "J2") (pin "10") (pinfunction "10_10") (pintype "passive"))
      (node (ref "U1") (pin "36") (pinfunction "MTDO/GPIO40/CLK_OUT2_36") (pintype "bidirectional"))
    )
    (net (code "50") (name "/GPIO41") (class "Default")
      (node (ref "J2") (pin "9") (pinfunction "9_9") (pintype "passive"))
      (node (ref "U1") (pin "37") (pinfunction "MTDI/GPIO41/CLK_OUT1_37") (pintype "bidirectional"))
    )
    (net (code "51") (name "/GPIO42") (class "Default")
      (node (ref "J2") (pin "8") (pinfunction "8_8") (pintype "passive"))
      (node (ref "U1") (pin "38") (pinfunction "MTMS/GPIO42_38") (pintype "bidirectional"))
    )
    (net (code "52") (name "/GPIO45") (class "Default")
      (node (ref "J2") (pin "5") (pinfunction "5_5") (pintype "passive"))
      (node (ref "U1") (pin "41") (pinfunction "GPIO45_41") (pintype "bidirectional"))
    )
    (net (code "53") (name "/GPIO46") (class "Default")
      (node (ref "J2") (pin "4") (pinfunction "4_4") (pintype "passive"))
      (node (ref "U1") (pin "44") (pinfunction "GPIO46_44") (pintype "bidirectional"))
    )
    (net (code "54") (name "/GPIO47") (class "Default")
      (node (ref "J2") (pin "23") (pinfunction "23_23") (pintype "passive"))
      (node (ref "U1") (pin "27") (pinfunction "GPIO47/SPICLK_P_DIFF/SUBSPICLK_P_DIFF_27") (pintype "bidirectional"))
    )
    (net (code "55") (name "/GPIO48") (class "Default")
      (node (ref "J2") (pin "22") (pinfunction "22_22") (pintype "passive"))
      (node (ref "U1") (pin "30") (pinfunction "GPIO48/SPICLK_N_DIFF/SUBSPICLK_N_DIFF_30") (pintype "bidirectional"))
    )
    (net (code "56") (name "/PR1") (class "Default")
      (node (ref "R19") (pin "2") (pinfunction "2_2") (pintype "passive"))
      (node (ref "R8") (pin "1") (pinfunction "1_1") (pintype "passive"))
      (node (ref "U4") (pin "4") (pinfunction "PR1_4") (pintype "input"))
    )
    (net (code "57") (name "/USB_CONN_D_N") (class "Default")
      (node (ref "J3") (pin "A7") (pinfunction "DN1_A7") (pintype "bidirectional"))
      (node (ref "J3") (pin "B7") (pinfunction "DN2_B7") (pintype "bidirectional"))
      (node (ref "U5") (pin "1") (pinfunction "I/O1_1") (pintype "bidirectional"))
    )
    (net (code "58") (name "/USB_CONN_D_P") (class "Default")
      (node (ref "J3") (pin "A6") (pinfunction "DP1_A6") (pintype "bidirectional"))
      (node (ref "J3") (pin "B6") (pinfunction "DP2_B6") (pintype "bidirectional"))
      (node (ref "U5") (pin "3") (pinfunction "I/O2_3") (pintype "bidirectional"))
    )
    (net (code "59") (name "/USB_ESD_D_N") (class "Default")
      (node (ref "R7") (pin "1") (pinfunction "1_1") (pintype "passive"))
      (node (ref "U5") (pin "6") (pinfunction "I/O1_6") (pintype "bidirectional"))
    )
    (net (code "60") (name "/USB_ESD_D_P") (class "Default")
      (node (ref "R6") (pin "1") (pinfunction "1_1") (pintype "passive"))
      (node (ref "U5") (pin "4") (pinfunction "I/O2_4") (pintype "bidirectional"))
    )
    (net (code "61") (name "/VBUS_SENSE") (class "Default")
      (node (ref "R10") (pin "1") (pinfunction "1_1") (pintype "passive"))
      (node (ref "R13") (pin "2") (pinfunction "2_2") (pintype "passive"))
      (node (ref "U2") (pin "16") (pinfunction "CBUS3_16") (pintype "bidirectional"))
    )
    (net (code "62") (name "/esp_N") (class "Default")
      (node (ref "R25") (pin "2") (pinfunction "2_2") (pintype "passive"))
      (node (ref "R27") (pin "2") (pinfunction "2_2") (pintype "passive"))
      (node (ref "U1") (pin "23") (pinfunction "USB_D-/GPIO19/RTC_GPIO19/U1RTS/ADC2_CH8/CLK_OUT2_23") (pintype "bidirectional"))
    )
    (net (code "63") (name "/esp_P") (class "Default")
      (node (ref "R24") (pin "2") (pinfunction "2_2") (pintype "passive"))
      (node (ref "R26") (pin "2") (pinfunction "2_2") (pintype "passive"))
      (node (ref "U1") (pin "24") (pinfunction "USB_D+/GPIO20/RTC_GPIO20/U1CTS/ADC2_CH9/CLK_OUT1_24") (pintype "bidirectional"))
    )
    (net (code "64") (name "3V3_REG") (class "Default")
      (node (ref "C12") (pin "2") (pinfunction "2_2") (pintype "passive"))
      (node (ref "C13") (pin "2") (pinfunction "2_2") (pintype "passive"))
      (node (ref "J6") (pin "2") (pinfunction "2_2") (pintype "passive"))
      (node (ref "R3") (pin "2") (pinfunction "2_2") (pintype "passive"))
      (node (ref "U3") (pin "3") (pinfunction "VOUT_3") (pintype "power_in"))
    )
    (net (code "65") (name "GND") (class "Default")
      (node (ref "C1") (pin "1") (pinfunction "1_1") (pintype "passive"))
      (node (ref "C10") (pin "1") (pinfunction "1_1") (pintype "passive"))
      (node (ref "C11") (pin "1") (pinfunction "1_1") (pintype "passive"))
      (node (ref "C12") (pin "1") (pinfunction "1_1") (pintype "passive"))
      (node (ref "C13") (pin "1") (pinfunction "1_1") (pintype "passive"))
      (node (ref "C14") (pin "1") (pinfunction "1_1") (pintype "passive"))
      (node (ref "C15") (pin "1") (pinfunction "1_1") (pintype "passive"))
      (node (ref "C16") (pin "1") (pinfunction "1_1") (pintype "passive"))
      (node (ref "C17") (pin "1") (pinfunction "1_1") (pintype "passive"))
      (node (ref "C18") (pin "1") (pinfunction "1_1") (pintype "passive"))
      (node (ref "C19") (pin "1") (pinfunction "1_1") (pintype "passive"))
      (node (ref "C2") (pin "1") (pinfunction "1_1") (pintype "passive"))
      (node (ref "C3") (pin "1") (pinfunction "1_1") (pintype "passive"))
      (node (ref "C4") (pin "1") (pinfunction "1_1") (pintype "passive"))
      (node (ref "C5") (pin "1") (pinfunction "1_1") (pintype "passive"))
      (node (ref "C6") (pin "1") (pinfunction "1_1") (pintype "passive"))
      (node (ref "C7") (pin "1") (pinfunction "1_1") (pintype "passive"))
      (node (ref "C8") (pin "1") (pinfunction "1_1") (pintype "passive"))
      (node (ref "C9") (pin "1") (pinfunction "1_1") (pintype "passive"))
      (node (ref "D1") (pin "2") (pinfunction "2_2") (pintype "passive"))
      (node (ref "J1") (pin "1") (pinfunction "1_1") (pintype "passive"))
      (node (ref "J1") (pin "23") (pinfunction "23_23") (pintype "passive"))
      (node (ref "J1") (pin "24") (pinfunction "24_24") (pintype "passive"))
      (node (ref "J2") (pin "2") (pinfunction "2_2") (pintype "passive"))
      (node (ref "J2") (pin "24") (pinfunction "24_24") (pintype "passive"))
      (node (ref "J3") (pin "A1/B12") (pinfunction "GND_A1/B12") (pintype "power_in"))
      (node (ref "J3") (pin "B1/A12") (pinfunction "GND_B1/A12") (pintype "power_in"))
      (node (ref "J3") (pin "SH") (pinfunction "SHIELD_SH") (pintype "passive"))
      (node (ref "J4") (pin "A1/B12") (pinfunction "GND_A1/B12") (pintype "power_in"))
      (node (ref "J4") (pin "B1/A12") (pinfunction "GND_B1/A12") (pintype "power_in"))
      (node (ref "J4") (pin "SH") (pinfunction "SHIELD_SH") (pintype "passive"))
      (node (ref "R11") (pin "1") (pinfunction "1_1") (pintype "passive"))
      (node (ref "R12") (pin "1") (pinfunction "1_1") (pintype "passive"))
      (node (ref "R13") (pin "1") (pinfunction "1_1") (pintype "passive"))
      (node (ref "R14") (pin "1") (pinfunction "1_1") (pintype "passive"))
      (node (ref "R15") (pin "1") (pinfunction "1_1") (pintype "passive"))
      (node (ref "R19") (pin "1") (pinfunction "1_1") (pintype "passive"))
      (node (ref "R9") (pin "1") (pinfunction "1_1") (pintype "passive"))
      (node (ref "SW1") (pin "1") (pinfunction "1_1") (pintype "passive"))
      (node (ref "SW2") (pin "1") (pinfunction "1_1") (pintype "passive"))
      (node (ref "U1") (pin "1") (pinfunction "GND_1") (pintype "power_in"))
      (node (ref "U2") (pin "3") (pinfunction "GND_3") (pintype "power_in"))
      (node (ref "U3") (pin "1") (pinfunction "GND_1") (pintype "power_in"))
      (node (ref "U4") (pin "1") (pinfunction "GND_1") (pintype "power_in"))
      (node (ref "U5") (pin "2") (pinfunction "GND_2") (pintype "power_in"))
      (node (ref "U6") (pin "2") (pinfunction "GND_2") (pintype "power_in"))
    )
    (net (code "66") (name "Net-(D1-Pad1)") (class "Default")
      (node (ref "D1") (pin "1") (pinfunction "1_1") (pintype "passive"))
      (node (ref "R3") (pin "1") (pinfunction "1_1") (pintype "passive"))
    )
    (net (code "67") (name "Net-(D2-Pad1)") (class "Default")
      (node (ref "D2") (pin "1") (pinfunction "1_1") (pintype "passive"))
      (node (ref "R4") (pin "1") (pinfunction "1_1") (pintype "passive"))
    )
    (net (code "68") (name "Net-(J3-CC1)") (class "Default")
      (node (ref "J3") (pin "A5") (pinfunction "CC1_A5") (pintype "bidirectional"))
      (node (ref "R12") (pin "2") (pinfunction "2_2") (pintype "passive"))
    )
    (net (code "69") (name "Net-(J3-CC2)") (class "Default")
      (node (ref "J3") (pin "B5") (pinfunction "CC2_B5") (pintype "bidirectional"))
      (node (ref "R11") (pin "2") (pinfunction "2_2") (pintype "passive"))
    )
    (net (code "70") (name "Net-(J4-CC1)") (class "Default")
      (node (ref "J4") (pin "A5") (pinfunction "CC1_A5") (pintype "bidirectional"))
      (node (ref "R15") (pin "2") (pinfunction "2_2") (pintype "passive"))
    )
    (net (code "71") (name "Net-(J4-CC2)") (class "Default")
      (node (ref "J4") (pin "B5") (pinfunction "CC2_B5") (pintype "bidirectional"))
      (node (ref "R14") (pin "2") (pinfunction "2_2") (pintype "passive"))
    )
    (net (code "72") (name "Net-(Q1-Pad1)") (class "Default")
      (node (ref "Q1") (pin "1") (pinfunction "1_1") (pintype "passive"))
      (node (ref "R16") (pin "2") (pinfunction "2_2") (pintype "passive"))
    )
    (net (code "73") (name "Net-(Q2-Pad1)") (class "Default")
      (node (ref "Q2") (pin "1") (pinfunction "1_1") (pintype "passive"))
      (node (ref "R18") (pin "2") (pinfunction "2_2") (pintype "passive"))
    )
    (net (code "74") (name "VBUS_1") (class "Default")
      (node (ref "C1") (pin "2") (pinfunction "2_2") (pintype "passive"))
      (node (ref "J3") (pin "A4/B9") (pinfunction "VBUS_A4/B9") (pintype "power_in"))
      (node (ref "J3") (pin "B4/A9") (pinfunction "VBUS_B4/A9") (pintype "power_in"))
      (node (ref "R10") (pin "2") (pinfunction "2_2") (pintype "passive"))
      (node (ref "R8") (pin "2") (pinfunction "2_2") (pintype "passive"))
      (node (ref "U4") (pin "3") (pinfunction "Vin1_3") (pintype "power_in"))
      (node (ref "U4") (pin "5") (pinfunction "MODE_5") (pintype "input"))
      (node (ref "U5") (pin "5") (pinfunction "VBUS_5") (pintype "power_in"))
    )
    (net (code "75") (name "VBUS_2") (class "Default")
      (node (ref "C10") (pin "2") (pinfunction "2_2") (pintype "passive"))
      (node (ref "J4") (pin "A4/B9") (pinfunction "VBUS_A4/B9") (pintype "power_in"))
      (node (ref "J4") (pin "B4/A9") (pinfunction "VBUS_B4/A9") (pintype "power_in"))
      (node (ref "U4") (pin "6") (pinfunction "Vin2_6") (pintype "power_in"))
      (node (ref "U6") (pin "5") (pinfunction "VBUS_5") (pintype "power_in"))
    )
    (net (code "76") (name "unconnected-(J3-SBU1-PadA8)") (class "Default")
      (node (ref "J3") (pin "A8") (pinfunction "SBU1_A8") (pintype "bidirectional+no_connect"))
    )
    (net (code "77") (name "unconnected-(J3-SBU2-PadB8)") (class "Default")
      (node (ref "J3") (pin "B8") (pinfunction "SBU2_B8") (pintype "bidirectional+no_connect"))
    )
    (net (code "78") (name "unconnected-(J4-SBU1-PadA8)") (class "Default")
      (node (ref "J4") (pin "A8") (pinfunction "SBU1_A8") (pintype "bidirectional+no_connect"))
    )
    (net (code "79") (name "unconnected-(J4-SBU2-PadB8)") (class "Default")
      (node (ref "J4") (pin "B8") (pinfunction "SBU2_B8") (pintype "bidirectional+no_connect"))
    )
    (net (code "80") (name "unconnected-(U2-CBUS1-Pad14)") (class "Default")
      (node (ref "U2") (pin "14") (pinfunction "CBUS1_14") (pintype "bidirectional+no_connect"))
    )
    (net (code "81") (name "unconnected-(U2-CBUS2-Pad7)") (class "Default")
      (node (ref "U2") (pin "7") (pinfunction "CBUS2_7") (pintype "bidirectional+no_connect"))
    )
    (net (code "82") (name "unconnected-(U2-~{CTS}-Pad6)") (class "Default")
      (node (ref "U2") (pin "6") (pinfunction "~{CTS}_6") (pintype "input+no_connect"))
    )
    (net (code "83") (name "unconnected-(U2-~{DCD}-Pad5)") (class "Default")
      (node (ref "U2") (pin "5") (pinfunction "~{DCD}_5") (pintype "input+no_connect"))
    )
    (net (code "84") (name "unconnected-(U2-~{DSR}-Pad4)") (class "Default")
      (node (ref "U2") (pin "4") (pinfunction "~{DSR}_4") (pintype "input+no_connect"))
    )
    (net (code "85") (name "unconnected-(U2-~{RI}-Pad2)") (class "Default")
      (node (ref "U2") (pin "2") (pinfunction "~{RI}_2") (pintype "input+no_connect"))
    )
    (net (code "86") (name "unconnected-(U4-ST-Pad8)") (class "Default")
      (node (ref "U4") (pin "8") (pinfunction "ST_8") (pintype "output+no_connect"))
    )
  )
)
